# booz_main_v1_2.net
KiCad netlist of a schematic drawn in EAGLE
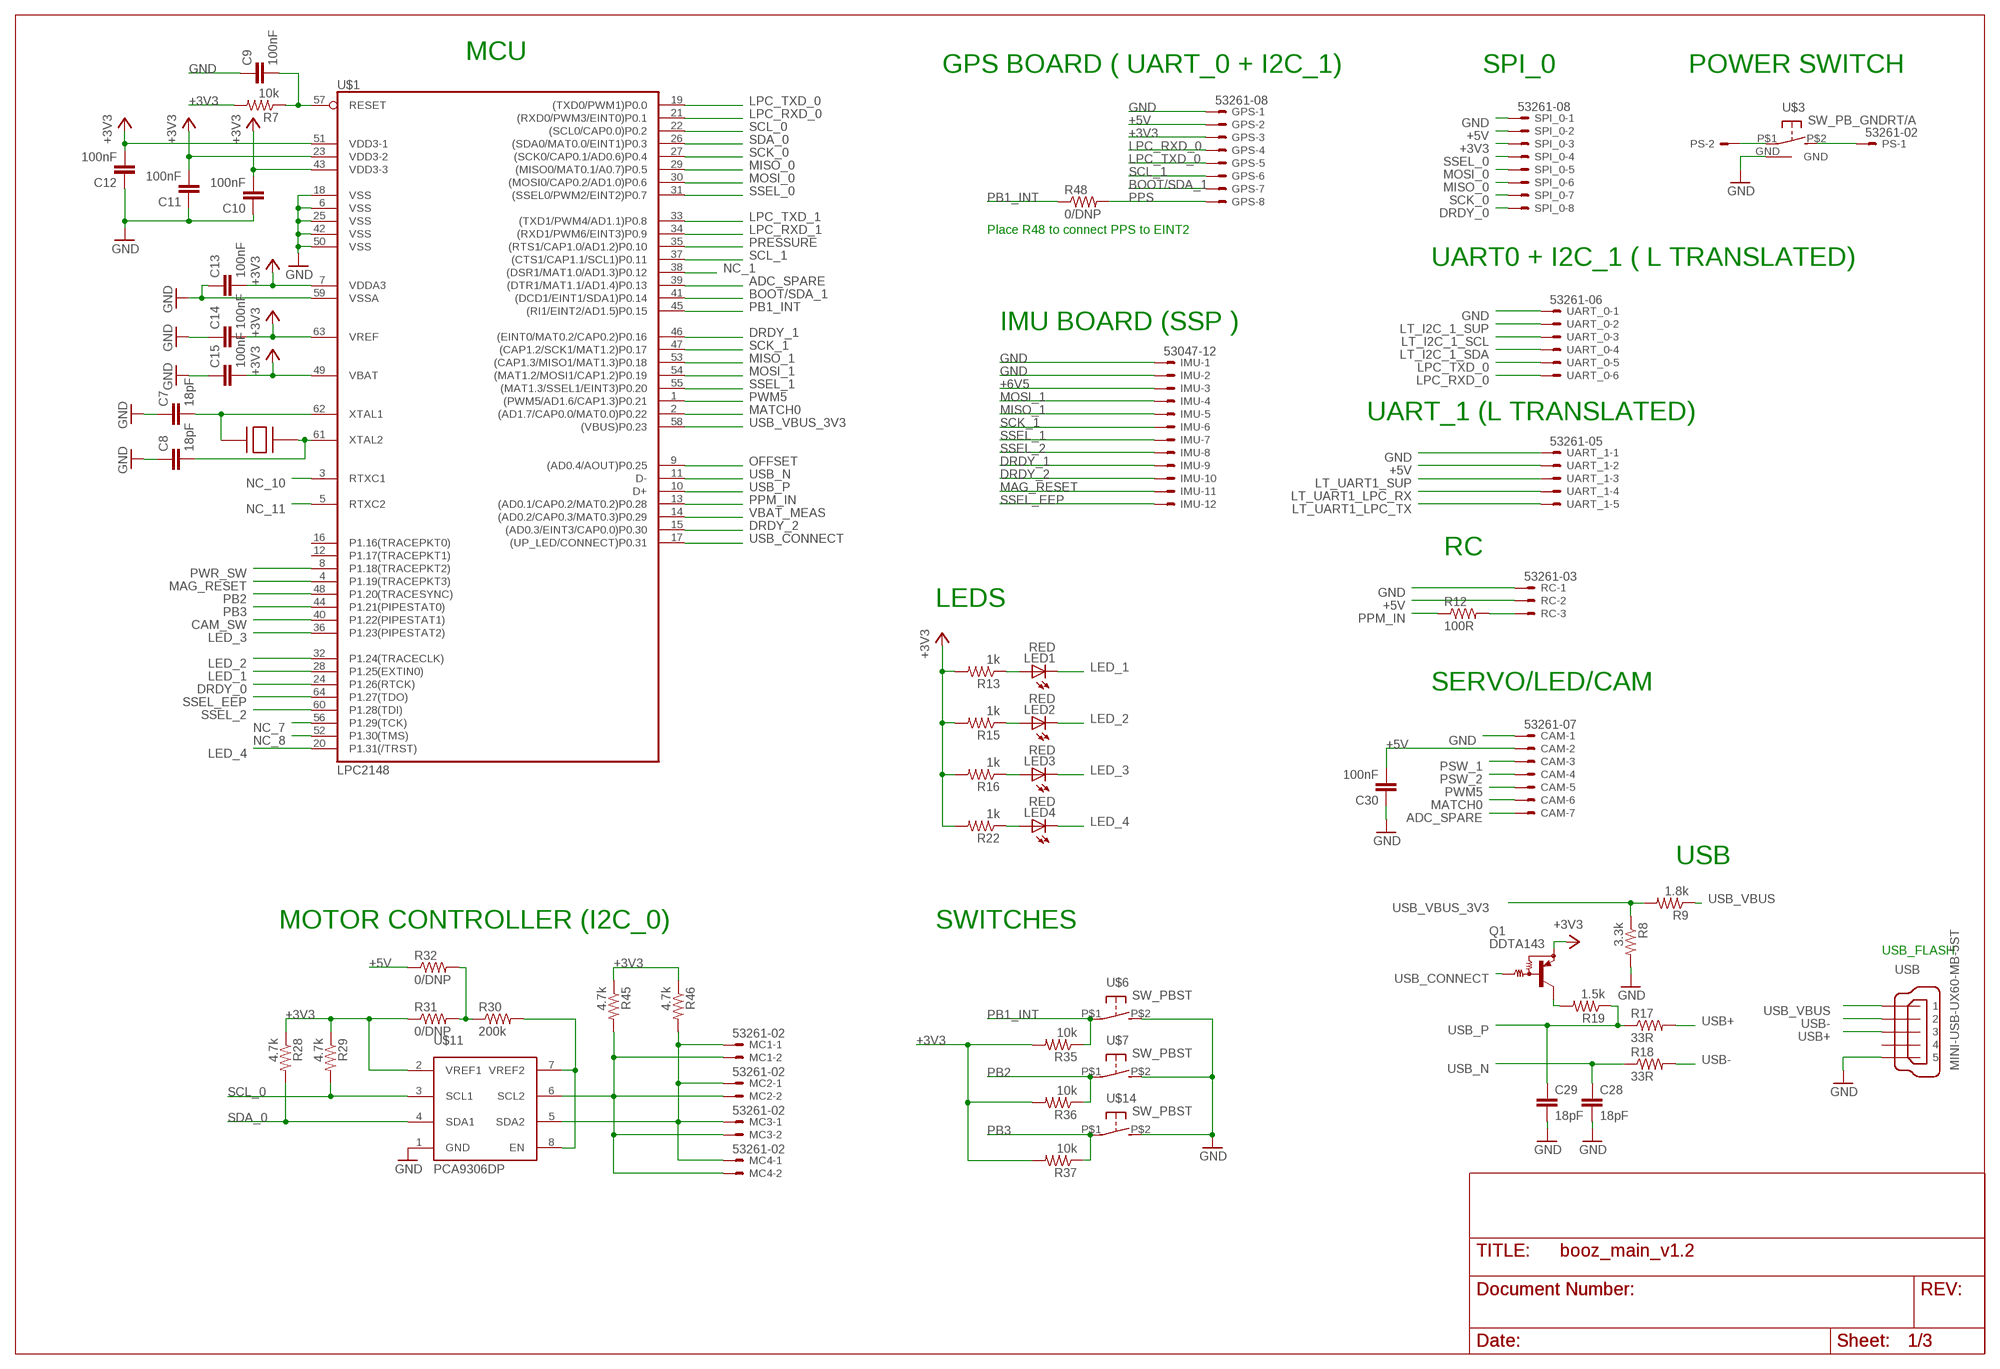
[diagram p0: schematic, sheet 1]
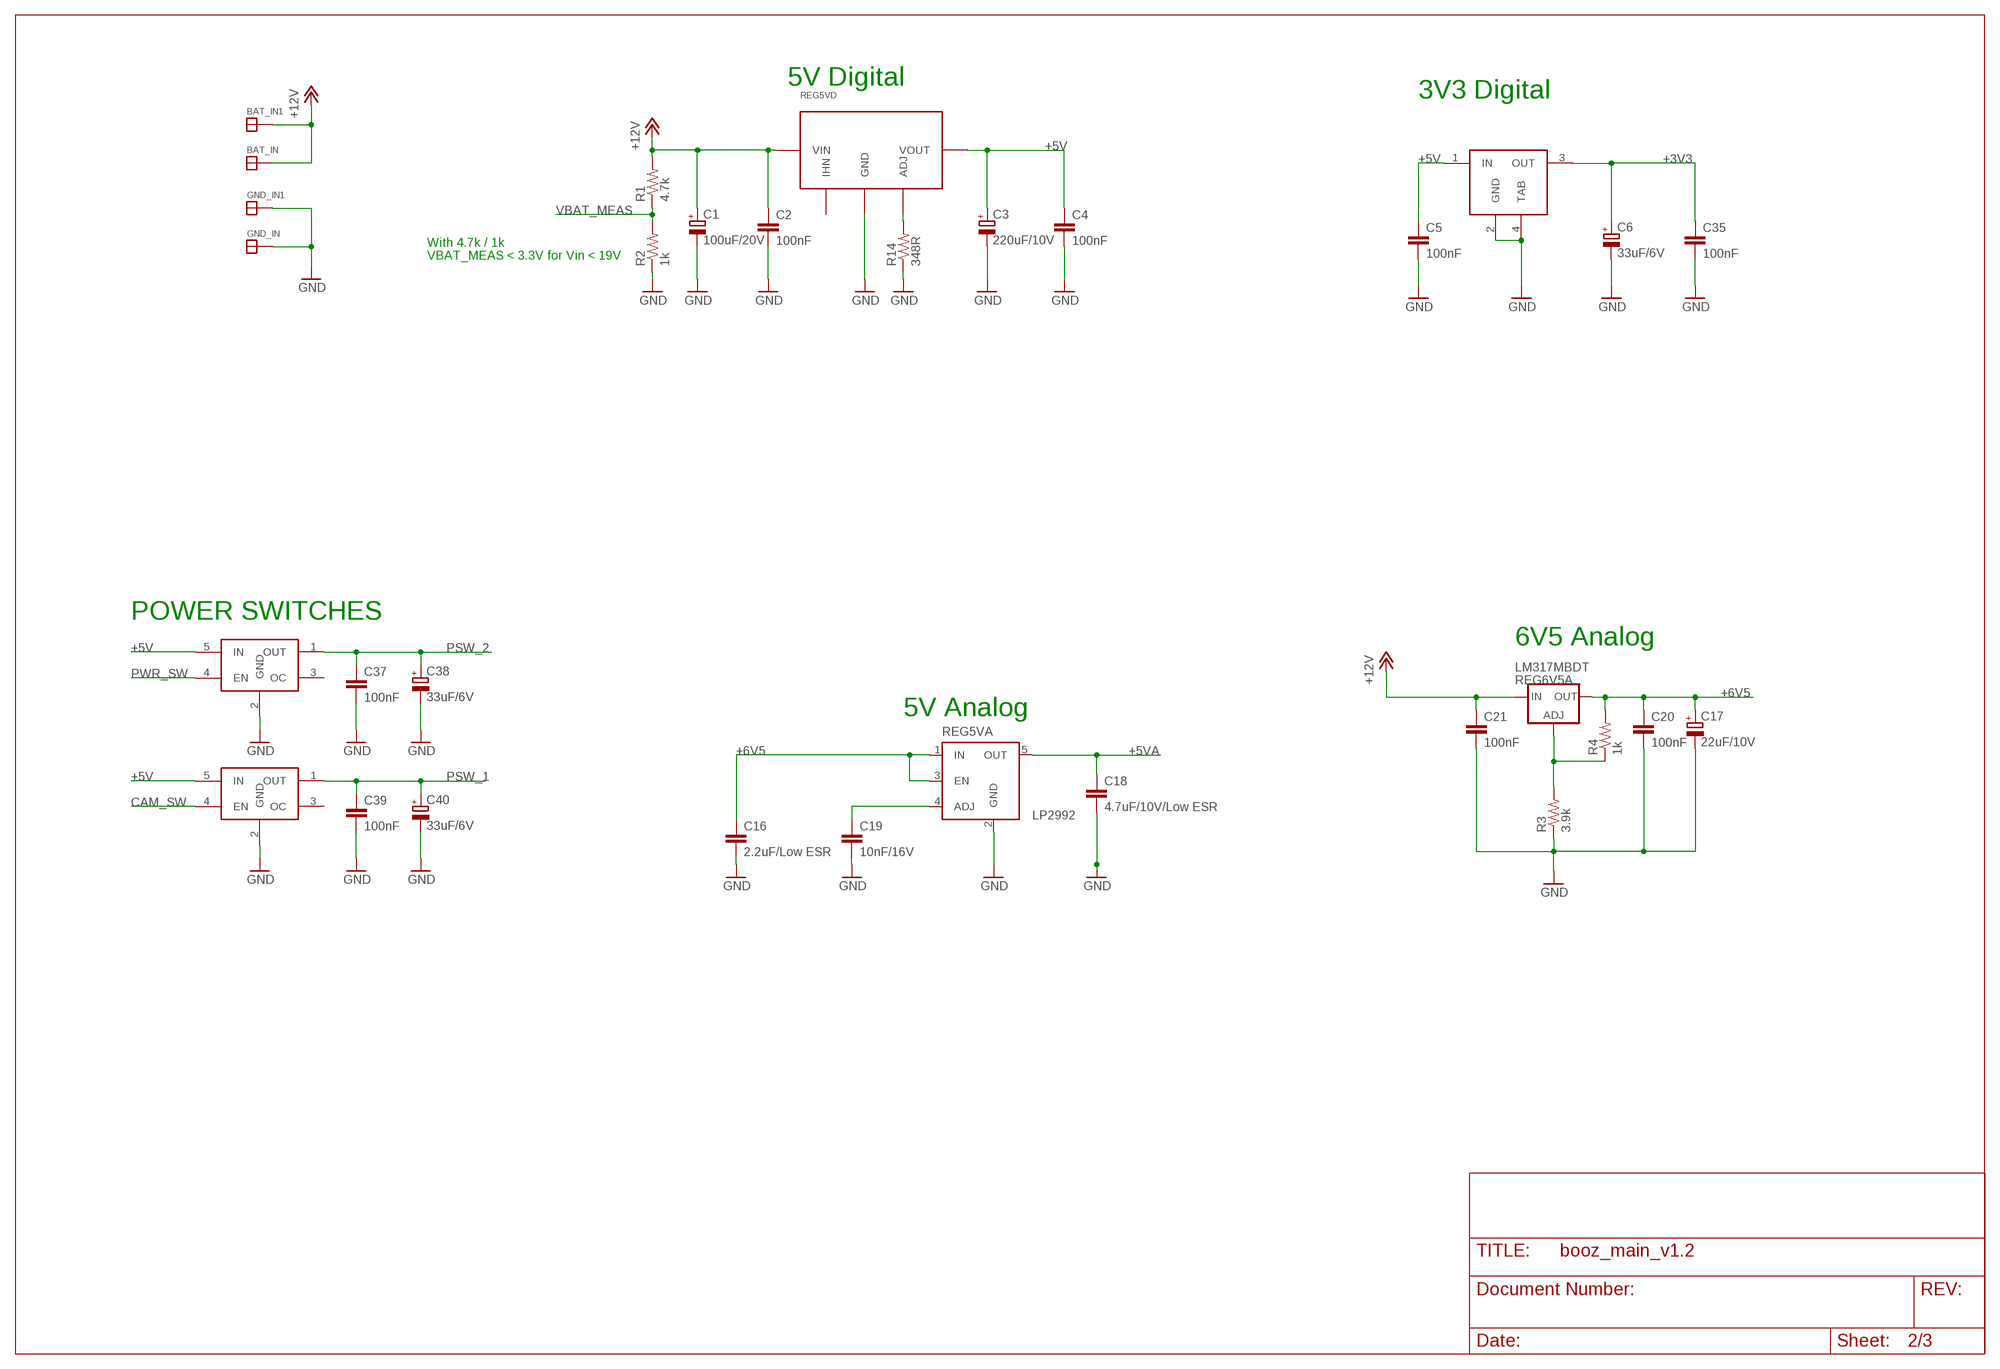
[diagram p1: schematic, sheet 2]
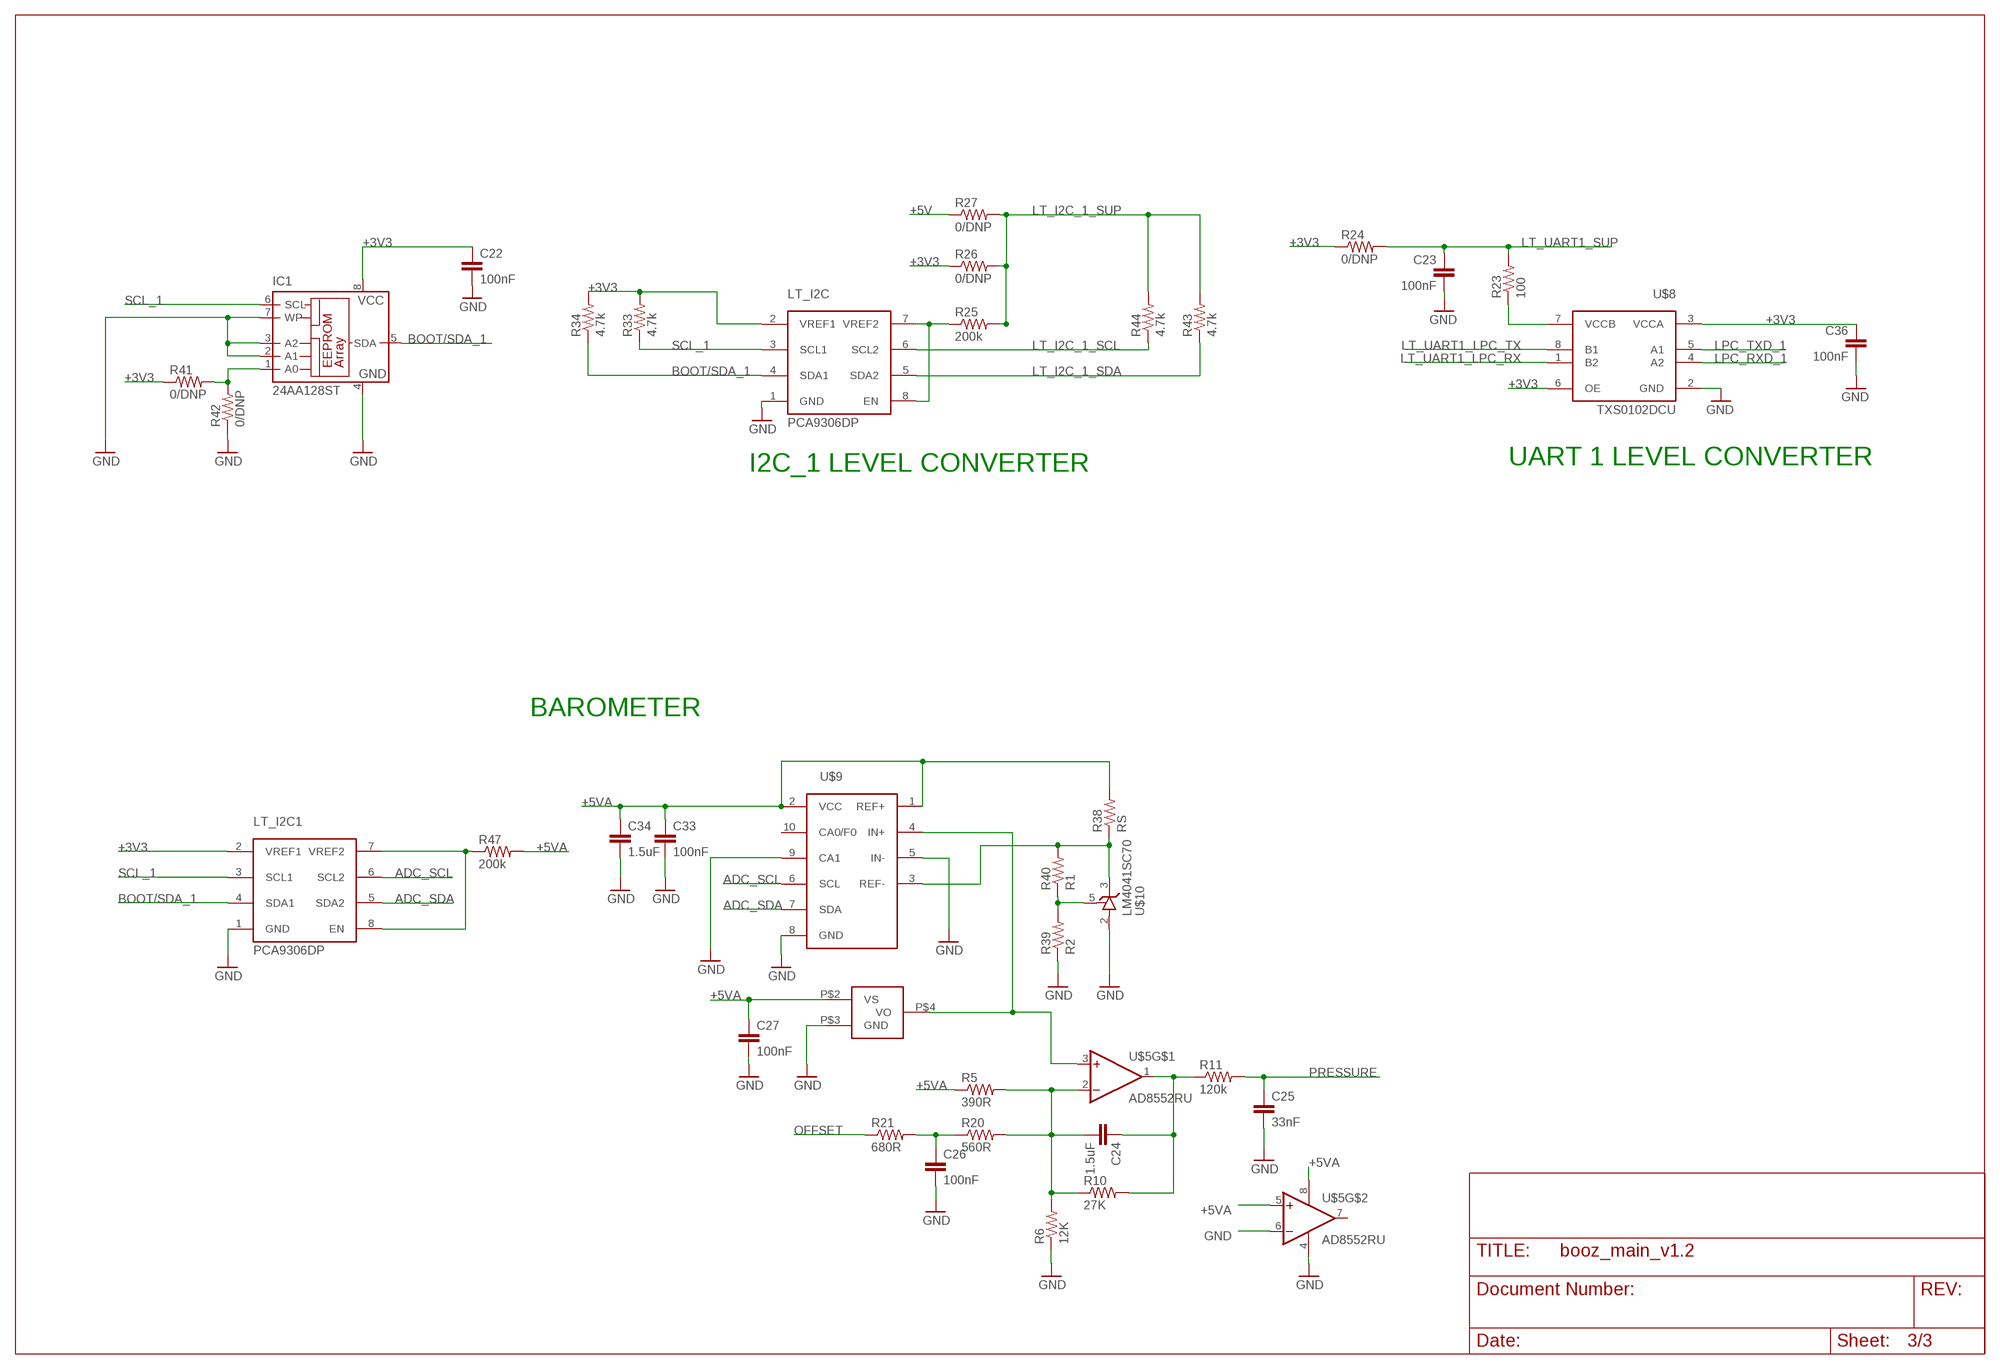
[diagram p2: schematic, sheet 3]

(export (version "E")
  (design (tool "Eeschema 10.0.6"))
  (components
    (comp (ref "BAT_IN")
      (value "SOLDER_PAD150_75")
      (footprint "eagle-import:SOLD_PAD_150_75")
      (libsource (lib "eagle-import") (part "SOLDER_PAD150_75"))
    )
    (comp (ref "BAT_IN1")
      (value "SOLDER_PAD150_75")
      (footprint "eagle-import:SOLD_PAD_150_75")
      (libsource (lib "eagle-import") (part "SOLDER_PAD150_75"))
    )
    (comp (ref "C1")
      (value "100uF/20V")
      (footprint "eagle-import:SMC_D")
      (libsource (lib "eagle-import") (part "CPOL-EUSMCD"))
    )
    (comp (ref "C2")
      (value "100nF")
      (footprint "eagle-import:C0603")
      (libsource (lib "eagle-import") (part "C-EUC0603"))
    )
    (comp (ref "C3")
      (value "220uF/10V")
      (footprint "eagle-import:SMC_D")
      (libsource (lib "eagle-import") (part "CPOL-EUSMCD"))
    )
    (comp (ref "C4")
      (value "100nF")
      (footprint "eagle-import:C0603")
      (libsource (lib "eagle-import") (part "C-EUC0603"))
    )
    (comp (ref "C5")
      (value "100nF")
      (footprint "eagle-import:C0603")
      (libsource (lib "eagle-import") (part "C-EUC0603"))
    )
    (comp (ref "C6")
      (value "33uF/6V")
      (footprint "eagle-import:CT3216")
      (libsource (lib "eagle-import") (part "CPOL-EUCT3216"))
    )
    (comp (ref "C16")
      (value "2.2uF/Low ESR")
      (footprint "eagle-import:C0603")
      (libsource (lib "eagle-import") (part "C-EUC0603"))
    )
    (comp (ref "C17")
      (value "22uF/10V")
      (footprint "eagle-import:CT3216")
      (libsource (lib "eagle-import") (part "CPOL-EUCT3216"))
    )
    (comp (ref "C18")
      (value "4.7uF/10V/Low ESR")
      (footprint "eagle-import:C0805K")
      (libsource (lib "eagle-import") (part "C-EUC0805K"))
    )
    (comp (ref "C19")
      (value "10nF/16V")
      (footprint "eagle-import:C0603K")
      (libsource (lib "eagle-import") (part "C-EUC0603K"))
    )
    (comp (ref "C20")
      (value "100nF")
      (footprint "eagle-import:C0603")
      (libsource (lib "eagle-import") (part "C-EUC0603"))
    )
    (comp (ref "C21")
      (value "100nF")
      (footprint "eagle-import:C0603")
      (libsource (lib "eagle-import") (part "C-EUC0603"))
    )
    (comp (ref "C35")
      (value "100nF")
      (footprint "eagle-import:C0603")
      (libsource (lib "eagle-import") (part "C-EUC0603"))
    )
    (comp (ref "C37")
      (value "100nF")
      (footprint "eagle-import:C0603")
      (libsource (lib "eagle-import") (part "C-EUC0603"))
    )
    (comp (ref "C38")
      (value "33uF/6V")
      (footprint "eagle-import:CT3216")
      (libsource (lib "eagle-import") (part "CPOL-EUCT3216"))
    )
    (comp (ref "C39")
      (value "100nF")
      (footprint "eagle-import:C0603")
      (libsource (lib "eagle-import") (part "C-EUC0603"))
    )
    (comp (ref "C40")
      (value "33uF/6V")
      (footprint "eagle-import:CT3216")
      (libsource (lib "eagle-import") (part "CPOL-EUCT3216"))
    )
    (comp (ref "GND_IN")
      (value "SOLDER_PAD150_75")
      (footprint "eagle-import:SOLD_PAD_150_75")
      (libsource (lib "eagle-import") (part "SOLDER_PAD150_75"))
    )
    (comp (ref "GND_IN1")
      (value "SOLDER_PAD150_75")
      (footprint "eagle-import:SOLD_PAD_150_75")
      (libsource (lib "eagle-import") (part "SOLDER_PAD150_75"))
    )
    (comp (ref "R1")
      (value "4.7k")
      (footprint "eagle-import:R0603")
      (libsource (lib "eagle-import") (part "R-US_R0603"))
    )
    (comp (ref "R2")
      (value "1k")
      (footprint "eagle-import:R0603")
      (libsource (lib "eagle-import") (part "R-US_R0603"))
    )
    (comp (ref "R3")
      (value "3.9k")
      (footprint "eagle-import:R0603")
      (libsource (lib "eagle-import") (part "R-US_R0603"))
    )
    (comp (ref "R4")
      (value "1k")
      (footprint "eagle-import:R0603")
      (libsource (lib "eagle-import") (part "R-US_R0603"))
    )
    (comp (ref "R14")
      (value "348R")
      (footprint "eagle-import:R0603")
      (libsource (lib "eagle-import") (part "R-US_R0603"))
    )
    (comp (ref "REG3V3D")
      (value "LM3940IMP-3.3")
      (footprint "eagle-import:SOT223-R")
      (libsource (lib "eagle-import") (part "LM3940IMP-3.3"))
    )
    (comp (ref "REG5VA")
      (value "LP2992")
      (footprint "eagle-import:SOT23-5")
      (libsource (lib "eagle-import") (part "MIC5219BM5"))
    )
    (comp (ref "REG5VD")
      (value "PTHTH")
      (footprint "eagle-import:PTH_TH")
      (libsource (lib "eagle-import") (part "PTHTH"))
    )
    (comp (ref "REG6V5A")
      (value "LM317MBDT")
      (footprint "eagle-import:DPACK")
      (libsource (lib "eagle-import") (part "LM317?MBDT"))
    )
    (comp (ref "U$12")
      (value "TPS2051B")
      (footprint "eagle-import:SOT23-5L")
      (libsource (lib "eagle-import") (part "TPS2051B"))
    )
    (comp (ref "U$13")
      (value "TPS2051B")
      (footprint "eagle-import:SOT23-5L")
      (libsource (lib "eagle-import") (part "TPS2051B"))
    )
    (comp (ref "C22")
      (value "100nF")
      (footprint "eagle-import:C0603")
      (libsource (lib "eagle-import") (part "C-EUC0603"))
    )
    (comp (ref "C23")
      (value "100nF")
      (footprint "eagle-import:C0603")
      (libsource (lib "eagle-import") (part "C-EUC0603"))
    )
    (comp (ref "C24")
      (value "1.5uF")
      (footprint "eagle-import:C0805")
      (libsource (lib "eagle-import") (part "C-EUC0805"))
    )
    (comp (ref "C25")
      (value "33nF")
      (footprint "eagle-import:C0805K")
      (libsource (lib "eagle-import") (part "C-EUC0805K"))
    )
    (comp (ref "C26")
      (value "100nF")
      (footprint "eagle-import:C0603")
      (libsource (lib "eagle-import") (part "C-EUC0603"))
    )
    (comp (ref "C27")
      (value "100nF")
      (footprint "eagle-import:C0603")
      (libsource (lib "eagle-import") (part "C-EUC0603"))
    )
    (comp (ref "C33")
      (value "100nF")
      (footprint "eagle-import:C0603")
      (libsource (lib "eagle-import") (part "C-EUC0603"))
    )
    (comp (ref "C34")
      (value "1.5uF")
      (footprint "eagle-import:C0805")
      (libsource (lib "eagle-import") (part "C-EUC0805"))
    )
    (comp (ref "C36")
      (value "100nF")
      (footprint "eagle-import:C0603")
      (libsource (lib "eagle-import") (part "C-EUC0603"))
    )
    (comp (ref "IC1")
      (value "24AA128ST")
      (footprint "eagle-import:TSSOP8")
      (libsource (lib "eagle-import") (part "24STAA128"))
    )
    (comp (ref "LT_I2C")
      (value "PCA9306DP")
      (footprint "eagle-import:TSSOP_B3")
      (libsource (lib "eagle-import") (part "PCA9306DP"))
    )
    (comp (ref "LT_I2C1")
      (value "PCA9306DP")
      (footprint "eagle-import:TSSOP_B3")
      (libsource (lib "eagle-import") (part "PCA9306DP"))
    )
    (comp (ref "R5")
      (value "390R")
      (footprint "eagle-import:R0603")
      (libsource (lib "eagle-import") (part "R-US_R0603"))
    )
    (comp (ref "R6")
      (value "12K")
      (footprint "eagle-import:R0603")
      (libsource (lib "eagle-import") (part "R-US_R0603"))
    )
    (comp (ref "R10")
      (value "27K")
      (footprint "eagle-import:R0603")
      (libsource (lib "eagle-import") (part "R-US_R0603"))
    )
    (comp (ref "R11")
      (value "120k")
      (footprint "eagle-import:R0603")
      (libsource (lib "eagle-import") (part "R-US_R0603"))
    )
    (comp (ref "R20")
      (value "560R")
      (footprint "eagle-import:R0603")
      (libsource (lib "eagle-import") (part "R-US_R0603"))
    )
    (comp (ref "R21")
      (value "680R")
      (footprint "eagle-import:R0603")
      (libsource (lib "eagle-import") (part "R-US_R0603"))
    )
    (comp (ref "R23")
      (value "100")
      (footprint "eagle-import:R0603")
      (libsource (lib "eagle-import") (part "R-US_R0603"))
    )
    (comp (ref "R24")
      (value "0/DNP")
      (footprint "eagle-import:R0603")
      (libsource (lib "eagle-import") (part "R-US_R0603"))
    )
    (comp (ref "R25")
      (value "200k")
      (footprint "eagle-import:R0603")
      (libsource (lib "eagle-import") (part "R-US_R0603"))
    )
    (comp (ref "R26")
      (value "0/DNP")
      (footprint "eagle-import:R0603")
      (libsource (lib "eagle-import") (part "R-US_R0603"))
    )
    (comp (ref "R27")
      (value "0/DNP")
      (footprint "eagle-import:R0603")
      (libsource (lib "eagle-import") (part "R-US_R0603"))
    )
    (comp (ref "R33")
      (value "4.7k")
      (footprint "eagle-import:R0603")
      (libsource (lib "eagle-import") (part "R-US_R0603"))
    )
    (comp (ref "R34")
      (value "4.7k")
      (footprint "eagle-import:R0603")
      (libsource (lib "eagle-import") (part "R-US_R0603"))
    )
    (comp (ref "R38")
      (value "RS")
      (footprint "eagle-import:R0603")
      (libsource (lib "eagle-import") (part "R-US_R0603"))
    )
    (comp (ref "R39")
      (value "R2")
      (footprint "eagle-import:R0603")
      (libsource (lib "eagle-import") (part "R-US_R0603"))
    )
    (comp (ref "R40")
      (value "R1")
      (footprint "eagle-import:R0603")
      (libsource (lib "eagle-import") (part "R-US_R0603"))
    )
    (comp (ref "R41")
      (value "0/DNP")
      (footprint "eagle-import:R0603")
      (libsource (lib "eagle-import") (part "R-US_R0603"))
    )
    (comp (ref "R42")
      (value "0/DNP")
      (footprint "eagle-import:R0603")
      (libsource (lib "eagle-import") (part "R-US_R0603"))
    )
    (comp (ref "R43")
      (value "4.7k")
      (footprint "eagle-import:R0603")
      (libsource (lib "eagle-import") (part "R-US_R0603"))
    )
    (comp (ref "R44")
      (value "4.7k")
      (footprint "eagle-import:R0603")
      (libsource (lib "eagle-import") (part "R-US_R0603"))
    )
    (comp (ref "R47")
      (value "200k")
      (footprint "eagle-import:R0603")
      (libsource (lib "eagle-import") (part "R-US_R0603"))
    )
    (comp (ref "U$2")
      (value "MPX6115")
      (footprint "eagle-import:CASE_1317")
      (libsource (lib "eagle-import") (part "MPX6115"))
    )
    (comp (ref "U$5")
      (value "AD8552RU")
      (footprint "eagle-import:TSSOP8")
      (libsource (lib "eagle-import") (part "AD8552RU"))
    )
    (comp (ref "U$8")
      (value "TXS0102DCU")
      (footprint "eagle-import:US8")
      (libsource (lib "eagle-import") (part "TXS0102DCU"))
    )
    (comp (ref "U$9")
      (value "LTC2485")
      (footprint "eagle-import:DFN10")
      (libsource (lib "eagle-import") (part "LTC2485"))
    )
    (comp (ref "U$10")
      (value "LM4041SC70")
      (footprint "eagle-import:SC70-5L")
      (libsource (lib "eagle-import") (part "LM4041SC70"))
    )
    (comp (ref "C7")
      (value "18pF")
      (footprint "eagle-import:C0603")
      (libsource (lib "eagle-import") (part "C-EUC0603"))
    )
    (comp (ref "C8")
      (value "18pF")
      (footprint "eagle-import:C0603")
      (libsource (lib "eagle-import") (part "C-EUC0603"))
    )
    (comp (ref "C9")
      (value "100nF")
      (footprint "eagle-import:C0603")
      (libsource (lib "eagle-import") (part "C-EUC0603"))
    )
    (comp (ref "C10")
      (value "100nF")
      (footprint "eagle-import:C0603")
      (libsource (lib "eagle-import") (part "C-EUC0603"))
    )
    (comp (ref "C11")
      (value "100nF")
      (footprint "eagle-import:C0603")
      (libsource (lib "eagle-import") (part "C-EUC0603"))
    )
    (comp (ref "C12")
      (value "100nF")
      (footprint "eagle-import:C0603")
      (libsource (lib "eagle-import") (part "C-EUC0603"))
    )
    (comp (ref "C13")
      (value "100nF")
      (footprint "eagle-import:C0603")
      (libsource (lib "eagle-import") (part "C-EUC0603"))
    )
    (comp (ref "C14")
      (value "100nF")
      (footprint "eagle-import:C0603")
      (libsource (lib "eagle-import") (part "C-EUC0603"))
    )
    (comp (ref "C15")
      (value "100nF")
      (footprint "eagle-import:C0603")
      (libsource (lib "eagle-import") (part "C-EUC0603"))
    )
    (comp (ref "C28")
      (value "18pF")
      (footprint "eagle-import:C0603")
      (libsource (lib "eagle-import") (part "C-EUC0603"))
    )
    (comp (ref "C29")
      (value "18pF")
      (footprint "eagle-import:C0603")
      (libsource (lib "eagle-import") (part "C-EUC0603"))
    )
    (comp (ref "C30")
      (value "100nF")
      (footprint "eagle-import:C0603")
      (libsource (lib "eagle-import") (part "C-EUC0603"))
    )
    (comp (ref "CAM")
      (value "53261-07")
      (footprint "eagle-import:53261-07")
      (libsource (lib "eagle-import") (part "53?-07261"))
    )
    (comp (ref "GPS")
      (value "53261-08")
      (footprint "eagle-import:53261-08")
      (libsource (lib "eagle-import") (part "53?-08261"))
    )
    (comp (ref "IMU")
      (value "53047-12")
      (footprint "eagle-import:53047-12")
      (libsource (lib "eagle-import") (part "53?-12047"))
    )
    (comp (ref "LED1")
      (value "RED")
      (footprint "eagle-import:CHIP-LED0805")
      (libsource (lib "eagle-import") (part "LEDCHIP-LED0805"))
    )
    (comp (ref "LED2")
      (value "RED")
      (footprint "eagle-import:CHIP-LED0805")
      (libsource (lib "eagle-import") (part "LEDCHIP-LED0805"))
    )
    (comp (ref "LED3")
      (value "RED")
      (footprint "eagle-import:CHIP-LED0805")
      (libsource (lib "eagle-import") (part "LEDCHIP-LED0805"))
    )
    (comp (ref "LED4")
      (value "RED")
      (footprint "eagle-import:CHIP-LED0805")
      (libsource (lib "eagle-import") (part "LEDCHIP-LED0805"))
    )
    (comp (ref "MC1")
      (value "53261-02")
      (footprint "eagle-import:53261-02")
      (libsource (lib "eagle-import") (part "53?-02261"))
    )
    (comp (ref "MC2")
      (value "53261-02")
      (footprint "eagle-import:53261-02")
      (libsource (lib "eagle-import") (part "53?-02261"))
    )
    (comp (ref "MC3")
      (value "53261-02")
      (footprint "eagle-import:53261-02")
      (libsource (lib "eagle-import") (part "53?-02261"))
    )
    (comp (ref "MC4")
      (value "53261-02")
      (footprint "eagle-import:53261-02")
      (libsource (lib "eagle-import") (part "53?-02261"))
    )
    (comp (ref "PS")
      (value "53261-02")
      (footprint "eagle-import:53261-02")
      (libsource (lib "eagle-import") (part "53?-02261"))
    )
    (comp (ref "Q1")
      (value "DDTA143")
      (footprint "eagle-import:SC59-BEC")
      (libsource (lib "eagle-import") (part "MUN2111T1"))
    )
    (comp (ref "R7")
      (value "10k")
      (footprint "eagle-import:R0603")
      (libsource (lib "eagle-import") (part "R-US_R0603"))
    )
    (comp (ref "R8")
      (value "3.3k")
      (footprint "eagle-import:R0603")
      (libsource (lib "eagle-import") (part "R-US_R0603"))
    )
    (comp (ref "R9")
      (value "1.8k")
      (footprint "eagle-import:R0603")
      (libsource (lib "eagle-import") (part "R-US_R0603"))
    )
    (comp (ref "R12")
      (value "100R")
      (footprint "eagle-import:R0603")
      (libsource (lib "eagle-import") (part "R-US_R0603"))
    )
    (comp (ref "R13")
      (value "1k")
      (footprint "eagle-import:R0603")
      (libsource (lib "eagle-import") (part "R-US_R0603"))
    )
    (comp (ref "R15")
      (value "1k")
      (footprint "eagle-import:R0603")
      (libsource (lib "eagle-import") (part "R-US_R0603"))
    )
    (comp (ref "R16")
      (value "1k")
      (footprint "eagle-import:R0603")
      (libsource (lib "eagle-import") (part "R-US_R0603"))
    )
    (comp (ref "R17")
      (value "33R")
      (footprint "eagle-import:R0603")
      (libsource (lib "eagle-import") (part "R-US_R0603"))
    )
    (comp (ref "R18")
      (value "33R")
      (footprint "eagle-import:R0603")
      (libsource (lib "eagle-import") (part "R-US_R0603"))
    )
    (comp (ref "R19")
      (value "1.5k")
      (footprint "eagle-import:R0603")
      (libsource (lib "eagle-import") (part "R-US_R0603"))
    )
    (comp (ref "R22")
      (value "1k")
      (footprint "eagle-import:R0603")
      (libsource (lib "eagle-import") (part "R-US_R0603"))
    )
    (comp (ref "R28")
      (value "4.7k")
      (footprint "eagle-import:R0603")
      (libsource (lib "eagle-import") (part "R-US_R0603"))
    )
    (comp (ref "R29")
      (value "4.7k")
      (footprint "eagle-import:R0603")
      (libsource (lib "eagle-import") (part "R-US_R0603"))
    )
    (comp (ref "R30")
      (value "200k")
      (footprint "eagle-import:R0603")
      (libsource (lib "eagle-import") (part "R-US_R0603"))
    )
    (comp (ref "R31")
      (value "0/DNP")
      (footprint "eagle-import:R0603")
      (libsource (lib "eagle-import") (part "R-US_R0603"))
    )
    (comp (ref "R32")
      (value "0/DNP")
      (footprint "eagle-import:R0603")
      (libsource (lib "eagle-import") (part "R-US_R0603"))
    )
    (comp (ref "R35")
      (value "10k")
      (footprint "eagle-import:R0603")
      (libsource (lib "eagle-import") (part "R-US_R0603"))
    )
    (comp (ref "R36")
      (value "10k")
      (footprint "eagle-import:R0603")
      (libsource (lib "eagle-import") (part "R-US_R0603"))
    )
    (comp (ref "R37")
      (value "10k")
      (footprint "eagle-import:R0603")
      (libsource (lib "eagle-import") (part "R-US_R0603"))
    )
    (comp (ref "R45")
      (value "4.7k")
      (footprint "eagle-import:R0603")
      (libsource (lib "eagle-import") (part "R-US_R0603"))
    )
    (comp (ref "R46")
      (value "4.7k")
      (footprint "eagle-import:R0603")
      (libsource (lib "eagle-import") (part "R-US_R0603"))
    )
    (comp (ref "R48")
      (value "0/DNP")
      (footprint "eagle-import:R0603")
      (libsource (lib "eagle-import") (part "R-US_R0603"))
    )
    (comp (ref "RC")
      (value "53261-03")
      (footprint "eagle-import:53261-03")
      (libsource (lib "eagle-import") (part "53?-03261"))
    )
    (comp (ref "SPI_0")
      (value "53261-08")
      (footprint "eagle-import:53261-08")
      (libsource (lib "eagle-import") (part "53?-08261"))
    )
    (comp (ref "U$1")
      (value "LPC2148")
      (footprint "eagle-import:SQFP-S-10X10-64")
      (libsource (lib "eagle-import") (part "LPC2148"))
    )
    (comp (ref "U$3")
      (value "SW_PB_GNDRT/A")
      (footprint "eagle-import:B3U-3100P")
      (libsource (lib "eagle-import") (part "SW_PB_GNDRT/A"))
    )
    (comp (ref "U$4")
      (value "CRYSTAL_CTS")
      (footprint "eagle-import:CTS_CRYSTAL")
      (libsource (lib "eagle-import") (part "CRYSTAL_CTS"))
    )
    (comp (ref "U$6")
      (value "SW_PBST")
      (footprint "eagle-import:B3U-1000P")
      (libsource (lib "eagle-import") (part "SW_PBST"))
    )
    (comp (ref "U$7")
      (value "SW_PBST")
      (footprint "eagle-import:B3U-1000P")
      (libsource (lib "eagle-import") (part "SW_PBST"))
    )
    (comp (ref "U$11")
      (value "PCA9306DP")
      (footprint "eagle-import:TSSOP_B3")
      (libsource (lib "eagle-import") (part "PCA9306DP"))
    )
    (comp (ref "U$14")
      (value "SW_PBST")
      (footprint "eagle-import:B3U-1000P")
      (libsource (lib "eagle-import") (part "SW_PBST"))
    )
    (comp (ref "UART_0")
      (value "53261-06")
      (footprint "eagle-import:53261-06")
      (libsource (lib "eagle-import") (part "53?-06261"))
    )
    (comp (ref "UART_1")
      (value "53261-05")
      (footprint "eagle-import:53261-05")
      (libsource (lib "eagle-import") (part "53?-05261"))
    )
    (comp (ref "USB")
      (value "MINI-USB-UX60-MB-5ST")
      (footprint "eagle-import:UX60-MB-5ST")
      (libsource (lib "eagle-import") (part "MINI-USB-UX60-MB-5ST"))
    )
  )
  (nets
    (net (code "1") (name "+3V3") (class "Default")
      (node (ref "C10") (pin "2") (pinfunction "2_2") (pintype "passive"))
      (node (ref "C11") (pin "2") (pinfunction "2_2") (pintype "passive"))
      (node (ref "C12") (pin "2") (pinfunction "2_2") (pintype "passive"))
      (node (ref "C13") (pin "2") (pinfunction "2_2") (pintype "passive"))
      (node (ref "C14") (pin "2") (pinfunction "2_2") (pintype "passive"))
      (node (ref "C15") (pin "2") (pinfunction "2_2") (pintype "passive"))
      (node (ref "C22") (pin "1") (pinfunction "1_1") (pintype "passive"))
      (node (ref "C35") (pin "1") (pinfunction "1_1") (pintype "passive"))
      (node (ref "C36") (pin "1") (pinfunction "1_1") (pintype "passive"))
      (node (ref "C6") (pin "+") (pinfunction "+_+") (pintype "passive"))
      (node (ref "GPS") (pin "3") (pinfunction "S_3") (pintype "passive"))
      (node (ref "IC1") (pin "8") (pinfunction "VCC_8") (pintype "power_in"))
      (node (ref "LT_I2C") (pin "2") (pinfunction "VREF1_2") (pintype "bidirectional"))
      (node (ref "LT_I2C1") (pin "2") (pinfunction "VREF1_2") (pintype "bidirectional"))
      (node (ref "Q1") (pin "E") (pinfunction "E_E") (pintype "passive"))
      (node (ref "R13") (pin "2") (pinfunction "2_2") (pintype "passive"))
      (node (ref "R15") (pin "2") (pinfunction "2_2") (pintype "passive"))
      (node (ref "R16") (pin "2") (pinfunction "2_2") (pintype "passive"))
      (node (ref "R22") (pin "2") (pinfunction "2_2") (pintype "passive"))
      (node (ref "R24") (pin "1") (pinfunction "1_1") (pintype "passive"))
      (node (ref "R26") (pin "1") (pinfunction "1_1") (pintype "passive"))
      (node (ref "R28") (pin "1") (pinfunction "1_1") (pintype "passive"))
      (node (ref "R29") (pin "1") (pinfunction "1_1") (pintype "passive"))
      (node (ref "R31") (pin "1") (pinfunction "1_1") (pintype "passive"))
      (node (ref "R33") (pin "2") (pinfunction "2_2") (pintype "passive"))
      (node (ref "R34") (pin "2") (pinfunction "2_2") (pintype "passive"))
      (node (ref "R35") (pin "2") (pinfunction "2_2") (pintype "passive"))
      (node (ref "R36") (pin "2") (pinfunction "2_2") (pintype "passive"))
      (node (ref "R37") (pin "2") (pinfunction "2_2") (pintype "passive"))
      (node (ref "R41") (pin "1") (pinfunction "1_1") (pintype "passive"))
      (node (ref "R45") (pin "1") (pinfunction "1_1") (pintype "passive"))
      (node (ref "R46") (pin "1") (pinfunction "1_1") (pintype "passive"))
      (node (ref "R7") (pin "2") (pinfunction "2_2") (pintype "passive"))
      (node (ref "REG3V3D") (pin "3") (pinfunction "OUT_3") (pintype "bidirectional"))
      (node (ref "SPI_0") (pin "3") (pinfunction "S_3") (pintype "passive"))
      (node (ref "U$1") (pin "23") (pinfunction "VDD3-2_23") (pintype "power_in"))
      (node (ref "U$1") (pin "43") (pinfunction "VDD3-3_43") (pintype "power_in"))
      (node (ref "U$1") (pin "49") (pinfunction "VBAT_49") (pintype "power_in"))
      (node (ref "U$1") (pin "51") (pinfunction "VDD3-1_51") (pintype "power_in"))
      (node (ref "U$1") (pin "63") (pinfunction "VREF_63") (pintype "input"))
      (node (ref "U$1") (pin "7") (pinfunction "VDDA3_7") (pintype "power_in"))
      (node (ref "U$11") (pin "2") (pinfunction "VREF1_2") (pintype "bidirectional"))
      (node (ref "U$8") (pin "3") (pinfunction "VCCA_3") (pintype "bidirectional"))
      (node (ref "U$8") (pin "6") (pinfunction "OE_6") (pintype "bidirectional"))
    )
    (net (code "2") (name "+5V") (class "Default")
      (node (ref "C3") (pin "+") (pinfunction "+_+") (pintype "passive"))
      (node (ref "C30") (pin "2") (pinfunction "2_2") (pintype "passive"))
      (node (ref "C4") (pin "1") (pinfunction "1_1") (pintype "passive"))
      (node (ref "C5") (pin "1") (pinfunction "1_1") (pintype "passive"))
      (node (ref "CAM") (pin "2") (pinfunction "S_2") (pintype "passive"))
      (node (ref "GPS") (pin "2") (pinfunction "S_2") (pintype "passive"))
      (node (ref "R27") (pin "1") (pinfunction "1_1") (pintype "passive"))
      (node (ref "R32") (pin "1") (pinfunction "1_1") (pintype "passive"))
      (node (ref "RC") (pin "2") (pinfunction "S_2") (pintype "passive"))
      (node (ref "REG3V3D") (pin "1") (pinfunction "IN_1") (pintype "bidirectional"))
      (node (ref "REG5VD") (pin "P$3") (pinfunction "VOUT_P$3") (pintype "bidirectional"))
      (node (ref "SPI_0") (pin "2") (pinfunction "S_2") (pintype "passive"))
      (node (ref "U$12") (pin "5") (pinfunction "IN_5") (pintype "bidirectional"))
      (node (ref "U$13") (pin "5") (pinfunction "IN_5") (pintype "bidirectional"))
      (node (ref "UART_1") (pin "2") (pinfunction "S_2") (pintype "passive"))
    )
    (net (code "3") (name "+5VA") (class "Default")
      (node (ref "C18") (pin "1") (pinfunction "1_1") (pintype "passive"))
      (node (ref "C27") (pin "1") (pinfunction "1_1") (pintype "passive"))
      (node (ref "C33") (pin "1") (pinfunction "1_1") (pintype "passive"))
      (node (ref "C34") (pin "1") (pinfunction "1_1") (pintype "passive"))
      (node (ref "R38") (pin "2") (pinfunction "2_2") (pintype "passive"))
      (node (ref "R47") (pin "2") (pinfunction "2_2") (pintype "passive"))
      (node (ref "R5") (pin "1") (pinfunction "1_1") (pintype "passive"))
      (node (ref "REG5VA") (pin "5") (pinfunction "OUT_5") (pintype "output"))
      (node (ref "U$2") (pin "P$2") (pinfunction "VS_P$2") (pintype "bidirectional"))
      (node (ref "U$5") (pin "5") (pinfunction "+IN_5") (pintype "input"))
      (node (ref "U$5") (pin "8") (pinfunction "V+_8") (pintype "power_in"))
      (node (ref "U$9") (pin "1") (pinfunction "REF+_1") (pintype "bidirectional"))
      (node (ref "U$9") (pin "2") (pinfunction "VCC_2") (pintype "bidirectional"))
    )
    (net (code "4") (name "+6V5") (class "Default")
      (node (ref "C16") (pin "1") (pinfunction "1_1") (pintype "passive"))
      (node (ref "C17") (pin "+") (pinfunction "+_+") (pintype "passive"))
      (node (ref "C20") (pin "1") (pinfunction "1_1") (pintype "passive"))
      (node (ref "IMU") (pin "3") (pinfunction "S_3") (pintype "passive"))
      (node (ref "R4") (pin "2") (pinfunction "2_2") (pintype "passive"))
      (node (ref "REG5VA") (pin "1") (pinfunction "IN_1") (pintype "input"))
      (node (ref "REG5VA") (pin "3") (pinfunction "EN_3") (pintype "input"))
      (node (ref "REG6V5A") (pin "4") (pinfunction "OUT_4") (pintype "passive"))
    )
    (net (code "5") (name "+12V") (class "Default")
      (node (ref "BAT_IN") (pin "P$1") (pinfunction "P$1_P$1") (pintype "bidirectional"))
      (node (ref "BAT_IN1") (pin "P$1") (pinfunction "P$1_P$1") (pintype "bidirectional"))
      (node (ref "C1") (pin "+") (pinfunction "+_+") (pintype "passive"))
      (node (ref "C2") (pin "1") (pinfunction "1_1") (pintype "passive"))
      (node (ref "C21") (pin "1") (pinfunction "1_1") (pintype "passive"))
      (node (ref "R1") (pin "2") (pinfunction "2_2") (pintype "passive"))
      (node (ref "REG5VD") (pin "P$1") (pinfunction "VIN_P$1") (pintype "bidirectional"))
      (node (ref "REG6V5A") (pin "3") (pinfunction "IN_3") (pintype "input"))
    )
    (net (code "6") (name "ADC_SCL") (class "Default")
      (node (ref "LT_I2C1") (pin "6") (pinfunction "SCL2_6") (pintype "bidirectional"))
      (node (ref "U$9") (pin "6") (pinfunction "SCL_6") (pintype "bidirectional"))
    )
    (net (code "7") (name "ADC_SDA") (class "Default")
      (node (ref "LT_I2C1") (pin "5") (pinfunction "SDA2_5") (pintype "bidirectional"))
      (node (ref "U$9") (pin "7") (pinfunction "SDA_7") (pintype "bidirectional"))
    )
    (net (code "8") (name "ADC_SPARE") (class "Default")
      (node (ref "CAM") (pin "7") (pinfunction "S_7") (pintype "passive"))
      (node (ref "U$1") (pin "39") (pinfunction "(DTR1/MAT1.1/AD1.4)P0.13_39") (pintype "bidirectional"))
    )
    (net (code "9") (name "BOOT{slash}SDA_1") (class "Default")
      (node (ref "GPS") (pin "7") (pinfunction "S_7") (pintype "passive"))
      (node (ref "IC1") (pin "5") (pinfunction "SDA_5") (pintype "bidirectional"))
      (node (ref "LT_I2C") (pin "4") (pinfunction "SDA1_4") (pintype "bidirectional"))
      (node (ref "LT_I2C1") (pin "4") (pinfunction "SDA1_4") (pintype "bidirectional"))
      (node (ref "R34") (pin "1") (pinfunction "1_1") (pintype "passive"))
      (node (ref "U$1") (pin "41") (pinfunction "(DCD1/EINT1/SDA1)P0.14_41") (pintype "bidirectional"))
    )
    (net (code "10") (name "CAM_SW") (class "Default")
      (node (ref "U$1") (pin "40") (pinfunction "P1.22(PIPESTAT1)_40") (pintype "bidirectional"))
      (node (ref "U$13") (pin "4") (pinfunction "EN_4") (pintype "bidirectional"))
    )
    (net (code "11") (name "DRDY_0") (class "Default")
      (node (ref "SPI_0") (pin "8") (pinfunction "S_8") (pintype "passive"))
      (node (ref "U$1") (pin "24") (pinfunction "P1.26(RTCK)_24") (pintype "bidirectional"))
    )
    (net (code "12") (name "DRDY_1") (class "Default")
      (node (ref "IMU") (pin "9") (pinfunction "S_9") (pintype "passive"))
      (node (ref "U$1") (pin "46") (pinfunction "(EINT0/MAT0.2/CAP0.2)P0.16_46") (pintype "bidirectional"))
    )
    (net (code "13") (name "DRDY_2") (class "Default")
      (node (ref "IMU") (pin "10") (pinfunction "S_10") (pintype "passive"))
      (node (ref "U$1") (pin "15") (pinfunction "(AD0.3/EINT3/CAP0.0)P0.30_15") (pintype "bidirectional"))
    )
    (net (code "14") (name "GND") (class "Default")
      (node (ref "C1") (pin "-") (pinfunction "-_-") (pintype "passive"))
      (node (ref "C10") (pin "1") (pinfunction "1_1") (pintype "passive"))
      (node (ref "C11") (pin "1") (pinfunction "1_1") (pintype "passive"))
      (node (ref "C12") (pin "1") (pinfunction "1_1") (pintype "passive"))
      (node (ref "C13") (pin "1") (pinfunction "1_1") (pintype "passive"))
      (node (ref "C14") (pin "1") (pinfunction "1_1") (pintype "passive"))
      (node (ref "C15") (pin "1") (pinfunction "1_1") (pintype "passive"))
      (node (ref "C16") (pin "2") (pinfunction "2_2") (pintype "passive"))
      (node (ref "C17") (pin "-") (pinfunction "-_-") (pintype "passive"))
      (node (ref "C18") (pin "2") (pinfunction "2_2") (pintype "passive"))
      (node (ref "C19") (pin "2") (pinfunction "2_2") (pintype "passive"))
      (node (ref "C2") (pin "2") (pinfunction "2_2") (pintype "passive"))
      (node (ref "C20") (pin "2") (pinfunction "2_2") (pintype "passive"))
      (node (ref "C21") (pin "2") (pinfunction "2_2") (pintype "passive"))
      (node (ref "C22") (pin "2") (pinfunction "2_2") (pintype "passive"))
      (node (ref "C23") (pin "2") (pinfunction "2_2") (pintype "passive"))
      (node (ref "C25") (pin "2") (pinfunction "2_2") (pintype "passive"))
      (node (ref "C26") (pin "2") (pinfunction "2_2") (pintype "passive"))
      (node (ref "C27") (pin "2") (pinfunction "2_2") (pintype "passive"))
      (node (ref "C28") (pin "2") (pinfunction "2_2") (pintype "passive"))
      (node (ref "C29") (pin "2") (pinfunction "2_2") (pintype "passive"))
      (node (ref "C3") (pin "-") (pinfunction "-_-") (pintype "passive"))
      (node (ref "C30") (pin "1") (pinfunction "1_1") (pintype "passive"))
      (node (ref "C33") (pin "2") (pinfunction "2_2") (pintype "passive"))
      (node (ref "C34") (pin "2") (pinfunction "2_2") (pintype "passive"))
      (node (ref "C35") (pin "2") (pinfunction "2_2") (pintype "passive"))
      (node (ref "C36") (pin "2") (pinfunction "2_2") (pintype "passive"))
      (node (ref "C37") (pin "2") (pinfunction "2_2") (pintype "passive"))
      (node (ref "C38") (pin "-") (pinfunction "-_-") (pintype "passive"))
      (node (ref "C39") (pin "2") (pinfunction "2_2") (pintype "passive"))
      (node (ref "C4") (pin "2") (pinfunction "2_2") (pintype "passive"))
      (node (ref "C40") (pin "-") (pinfunction "-_-") (pintype "passive"))
      (node (ref "C5") (pin "2") (pinfunction "2_2") (pintype "passive"))
      (node (ref "C6") (pin "-") (pinfunction "-_-") (pintype "passive"))
      (node (ref "C7") (pin "1") (pinfunction "1_1") (pintype "passive"))
      (node (ref "C8") (pin "1") (pinfunction "1_1") (pintype "passive"))
      (node (ref "C9") (pin "1") (pinfunction "1_1") (pintype "passive"))
      (node (ref "CAM") (pin "1") (pinfunction "S_1") (pintype "passive"))
      (node (ref "GND_IN") (pin "P$1") (pinfunction "P$1_P$1") (pintype "bidirectional"))
      (node (ref "GND_IN1") (pin "P$1") (pinfunction "P$1_P$1") (pintype "bidirectional"))
      (node (ref "GPS") (pin "1") (pinfunction "S_1") (pintype "passive"))
      (node (ref "IC1") (pin "2") (pinfunction "A1_2") (pintype "input"))
      (node (ref "IC1") (pin "3") (pinfunction "A2_3") (pintype "input"))
      (node (ref "IC1") (pin "4") (pinfunction "GND_4") (pintype "power_in"))
      (node (ref "IC1") (pin "7") (pinfunction "WP_7") (pintype "input"))
      (node (ref "IMU") (pin "1") (pinfunction "S_1") (pintype "passive"))
      (node (ref "IMU") (pin "2") (pinfunction "S_2") (pintype "passive"))
      (node (ref "LT_I2C") (pin "1") (pinfunction "GND_1") (pintype "bidirectional"))
      (node (ref "LT_I2C1") (pin "1") (pinfunction "GND_1") (pintype "bidirectional"))
      (node (ref "R14") (pin "1") (pinfunction "1_1") (pintype "passive"))
      (node (ref "R2") (pin "1") (pinfunction "1_1") (pintype "passive"))
      (node (ref "R3") (pin "1") (pinfunction "1_1") (pintype "passive"))
      (node (ref "R39") (pin "1") (pinfunction "1_1") (pintype "passive"))
      (node (ref "R42") (pin "1") (pinfunction "1_1") (pintype "passive"))
      (node (ref "R6") (pin "1") (pinfunction "1_1") (pintype "passive"))
      (node (ref "R8") (pin "2") (pinfunction "2_2") (pintype "passive"))
      (node (ref "RC") (pin "1") (pinfunction "S_1") (pintype "passive"))
      (node (ref "REG3V3D") (pin "2") (pinfunction "GND_2") (pintype "bidirectional"))
      (node (ref "REG3V3D") (pin "4") (pinfunction "TAB_4") (pintype "bidirectional"))
      (node (ref "REG5VA") (pin "2") (pinfunction "GND_2") (pintype "power_in"))
      (node (ref "REG5VD") (pin "P$2") (pinfunction "GND_P$2") (pintype "bidirectional"))
      (node (ref "SPI_0") (pin "1") (pinfunction "S_1") (pintype "passive"))
      (node (ref "U$1") (pin "18") (pinfunction "VSS_18") (pintype "power_in"))
      (node (ref "U$1") (pin "25") (pinfunction "VSS_25") (pintype "power_in"))
      (node (ref "U$1") (pin "42") (pinfunction "VSS_42") (pintype "power_in"))
      (node (ref "U$1") (pin "50") (pinfunction "VSS_50") (pintype "power_in"))
      (node (ref "U$1") (pin "59") (pinfunction "VSSA_59") (pintype "power_in"))
      (node (ref "U$1") (pin "6") (pinfunction "VSS_6") (pintype "power_in"))
      (node (ref "U$10") (pin "2") (pinfunction "A_2") (pintype "passive"))
      (node (ref "U$11") (pin "1") (pinfunction "GND_1") (pintype "bidirectional"))
      (node (ref "U$12") (pin "2") (pinfunction "GND_2") (pintype "bidirectional"))
      (node (ref "U$13") (pin "2") (pinfunction "GND_2") (pintype "bidirectional"))
      (node (ref "U$14") (pin "P$2") (pinfunction "S_P$2") (pintype "passive"))
      (node (ref "U$2") (pin "P$3") (pinfunction "GND_P$3") (pintype "bidirectional"))
      (node (ref "U$3") (pin "GND") (pinfunction "GND_GND") (pintype "passive"))
      (node (ref "U$5") (pin "4") (pinfunction "V-_4") (pintype "power_in"))
      (node (ref "U$5") (pin "6") (pinfunction "-IN_6") (pintype "input"))
      (node (ref "U$6") (pin "P$2") (pinfunction "S_P$2") (pintype "passive"))
      (node (ref "U$7") (pin "P$2") (pinfunction "S_P$2") (pintype "passive"))
      (node (ref "U$8") (pin "2") (pinfunction "GND_2") (pintype "bidirectional"))
      (node (ref "U$9") (pin "5") (pinfunction "IN-_5") (pintype "bidirectional"))
      (node (ref "U$9") (pin "8") (pinfunction "GND_8") (pintype "bidirectional"))
      (node (ref "U$9") (pin "9") (pinfunction "CA1_9") (pintype "bidirectional"))
      (node (ref "UART_0") (pin "1") (pinfunction "S_1") (pintype "passive"))
      (node (ref "UART_1") (pin "1") (pinfunction "S_1") (pintype "passive"))
      (node (ref "USB") (pin "5") (pinfunction "5_5") (pintype "input"))
    )
    (net (code "15") (name "LED_1") (class "Default")
      (node (ref "LED1") (pin "C") (pinfunction "C_C") (pintype "passive"))
      (node (ref "U$1") (pin "28") (pinfunction "P1.25(EXTIN0)_28") (pintype "bidirectional"))
    )
    (net (code "16") (name "LED_2") (class "Default")
      (node (ref "LED2") (pin "C") (pinfunction "C_C") (pintype "passive"))
      (node (ref "U$1") (pin "32") (pinfunction "P1.24(TRACECLK)_32") (pintype "bidirectional"))
    )
    (net (code "17") (name "LED_3") (class "Default")
      (node (ref "LED3") (pin "C") (pinfunction "C_C") (pintype "passive"))
      (node (ref "U$1") (pin "36") (pinfunction "P1.23(PIPESTAT2)_36") (pintype "bidirectional"))
    )
    (net (code "18") (name "LED_4") (class "Default")
      (node (ref "LED4") (pin "C") (pinfunction "C_C") (pintype "passive"))
      (node (ref "U$1") (pin "20") (pinfunction "P1.31(/TRST)_20") (pintype "bidirectional"))
    )
    (net (code "19") (name "LPC_RXD_0") (class "Default")
      (node (ref "GPS") (pin "4") (pinfunction "S_4") (pintype "passive"))
      (node (ref "U$1") (pin "21") (pinfunction "(RXD0/PWM3/EINT0)P0.1_21") (pintype "bidirectional"))
      (node (ref "UART_0") (pin "6") (pinfunction "S_6") (pintype "passive"))
    )
    (net (code "20") (name "LPC_RXD_1") (class "Default")
      (node (ref "U$1") (pin "34") (pinfunction "(RXD1/PWM6/EINT3)P0.9_34") (pintype "bidirectional"))
      (node (ref "U$8") (pin "4") (pinfunction "A2_4") (pintype "bidirectional"))
    )
    (net (code "21") (name "LPC_TXD_0") (class "Default")
      (node (ref "GPS") (pin "5") (pinfunction "S_5") (pintype "passive"))
      (node (ref "U$1") (pin "19") (pinfunction "(TXD0/PWM1)P0.0_19") (pintype "bidirectional"))
      (node (ref "UART_0") (pin "5") (pinfunction "S_5") (pintype "passive"))
    )
    (net (code "22") (name "LPC_TXD_1") (class "Default")
      (node (ref "U$1") (pin "33") (pinfunction "(TXD1/PWM4/AD1.1)P0.8_33") (pintype "bidirectional"))
      (node (ref "U$8") (pin "5") (pinfunction "A1_5") (pintype "bidirectional"))
    )
    (net (code "23") (name "LT_I2C_1_SCL") (class "Default")
      (node (ref "LT_I2C") (pin "6") (pinfunction "SCL2_6") (pintype "bidirectional"))
      (node (ref "R44") (pin "1") (pinfunction "1_1") (pintype "passive"))
      (node (ref "UART_0") (pin "3") (pinfunction "S_3") (pintype "passive"))
    )
    (net (code "24") (name "LT_I2C_1_SDA") (class "Default")
      (node (ref "LT_I2C") (pin "5") (pinfunction "SDA2_5") (pintype "bidirectional"))
      (node (ref "R43") (pin "1") (pinfunction "1_1") (pintype "passive"))
      (node (ref "UART_0") (pin "4") (pinfunction "S_4") (pintype "passive"))
    )
    (net (code "25") (name "LT_I2C_1_SUP") (class "Default")
      (node (ref "R25") (pin "2") (pinfunction "2_2") (pintype "passive"))
      (node (ref "R26") (pin "2") (pinfunction "2_2") (pintype "passive"))
      (node (ref "R27") (pin "2") (pinfunction "2_2") (pintype "passive"))
      (node (ref "R43") (pin "2") (pinfunction "2_2") (pintype "passive"))
      (node (ref "R44") (pin "2") (pinfunction "2_2") (pintype "passive"))
      (node (ref "UART_0") (pin "2") (pinfunction "S_2") (pintype "passive"))
    )
    (net (code "26") (name "LT_UART1_LPC_RX") (class "Default")
      (node (ref "U$8") (pin "1") (pinfunction "B2_1") (pintype "bidirectional"))
      (node (ref "UART_1") (pin "4") (pinfunction "S_4") (pintype "passive"))
    )
    (net (code "27") (name "LT_UART1_LPC_TX") (class "Default")
      (node (ref "U$8") (pin "8") (pinfunction "B1_8") (pintype "bidirectional"))
      (node (ref "UART_1") (pin "5") (pinfunction "S_5") (pintype "passive"))
    )
    (net (code "28") (name "LT_UART1_SUP") (class "Default")
      (node (ref "C23") (pin "1") (pinfunction "1_1") (pintype "passive"))
      (node (ref "R23") (pin "2") (pinfunction "2_2") (pintype "passive"))
      (node (ref "R24") (pin "2") (pinfunction "2_2") (pintype "passive"))
      (node (ref "UART_1") (pin "3") (pinfunction "S_3") (pintype "passive"))
    )
    (net (code "29") (name "MAG_RESET") (class "Default")
      (node (ref "IMU") (pin "11") (pinfunction "S_11") (pintype "passive"))
      (node (ref "U$1") (pin "4") (pinfunction "P1.19(TRACEPKT3)_4") (pintype "bidirectional"))
    )
    (net (code "30") (name "MATCH0") (class "Default")
      (node (ref "CAM") (pin "6") (pinfunction "S_6") (pintype "passive"))
      (node (ref "U$1") (pin "2") (pinfunction "(AD1.7/CAP0.0/MAT0.0)P0.22_2") (pintype "bidirectional"))
    )
    (net (code "31") (name "MISO_0") (class "Default")
      (node (ref "SPI_0") (pin "6") (pinfunction "S_6") (pintype "passive"))
      (node (ref "U$1") (pin "29") (pinfunction "(MISO0/MAT0.1/A0.7)P0.5_29") (pintype "bidirectional"))
    )
    (net (code "32") (name "MISO_1") (class "Default")
      (node (ref "IMU") (pin "5") (pinfunction "S_5") (pintype "passive"))
      (node (ref "U$1") (pin "53") (pinfunction "(CAP1.3/MISO1/MAT1.3)P0.18_53") (pintype "bidirectional"))
    )
    (net (code "33") (name "MOSI_0") (class "Default")
      (node (ref "SPI_0") (pin "5") (pinfunction "S_5") (pintype "passive"))
      (node (ref "U$1") (pin "30") (pinfunction "(MOSI0/CAP0.2/AD1.0)P0.6_30") (pintype "bidirectional"))
    )
    (net (code "34") (name "MOSI_1") (class "Default")
      (node (ref "IMU") (pin "4") (pinfunction "S_4") (pintype "passive"))
      (node (ref "U$1") (pin "54") (pinfunction "(MAT1.2/MOSI1/CAP1.2)P0.19_54") (pintype "bidirectional"))
    )
    (net (code "35") (name "NC_1") (class "Default")
      (node (ref "U$1") (pin "38") (pinfunction "(DSR1/MAT1.0/AD1.3)P0.12_38") (pintype "bidirectional"))
    )
    (net (code "36") (name "NC_7") (class "Default")
      (node (ref "U$1") (pin "56") (pinfunction "P1.29(TCK)_56") (pintype "bidirectional"))
    )
    (net (code "37") (name "NC_8") (class "Default")
      (node (ref "U$1") (pin "52") (pinfunction "P1.30(TMS)_52") (pintype "bidirectional"))
    )
    (net (code "38") (name "NC_10") (class "Default")
      (node (ref "U$1") (pin "3") (pinfunction "RTXC1_3") (pintype "input"))
    )
    (net (code "39") (name "NC_11") (class "Default")
      (node (ref "U$1") (pin "5") (pinfunction "RTXC2_5") (pintype "output"))
    )
    (net (code "40") (name "Net-(C26-Pad1)") (class "Default")
      (node (ref "C26") (pin "1") (pinfunction "1_1") (pintype "passive"))
      (node (ref "R20") (pin "1") (pinfunction "1_1") (pintype "passive"))
      (node (ref "R21") (pin "2") (pinfunction "2_2") (pintype "passive"))
    )
    (net (code "41") (name "Net-(IC1-A0)") (class "Default")
      (node (ref "IC1") (pin "1") (pinfunction "A0_1") (pintype "input"))
      (node (ref "R41") (pin "2") (pinfunction "2_2") (pintype "passive"))
      (node (ref "R42") (pin "2") (pinfunction "2_2") (pintype "passive"))
    )
    (net (code "42") (name "Net-(LED1-PadA)") (class "Default")
      (node (ref "LED1") (pin "A") (pinfunction "A_A") (pintype "passive"))
      (node (ref "R13") (pin "1") (pinfunction "1_1") (pintype "passive"))
    )
    (net (code "43") (name "Net-(LED2-PadA)") (class "Default")
      (node (ref "LED2") (pin "A") (pinfunction "A_A") (pintype "passive"))
      (node (ref "R15") (pin "1") (pinfunction "1_1") (pintype "passive"))
    )
    (net (code "44") (name "Net-(LED3-PadA)") (class "Default")
      (node (ref "LED3") (pin "A") (pinfunction "A_A") (pintype "passive"))
      (node (ref "R16") (pin "1") (pinfunction "1_1") (pintype "passive"))
    )
    (net (code "45") (name "Net-(LED4-PadA)") (class "Default")
      (node (ref "LED4") (pin "A") (pinfunction "A_A") (pintype "passive"))
      (node (ref "R22") (pin "1") (pinfunction "1_1") (pintype "passive"))
    )
    (net (code "46") (name "Net-(LT_I2C-EN)") (class "Default")
      (node (ref "LT_I2C") (pin "7") (pinfunction "VREF2_7") (pintype "bidirectional"))
      (node (ref "LT_I2C") (pin "8") (pinfunction "EN_8") (pintype "bidirectional"))
      (node (ref "R25") (pin "1") (pinfunction "1_1") (pintype "passive"))
    )
    (net (code "47") (name "Net-(LT_I2C1-EN)") (class "Default")
      (node (ref "LT_I2C1") (pin "7") (pinfunction "VREF2_7") (pintype "bidirectional"))
      (node (ref "LT_I2C1") (pin "8") (pinfunction "EN_8") (pintype "bidirectional"))
      (node (ref "R47") (pin "1") (pinfunction "1_1") (pintype "passive"))
    )
    (net (code "48") (name "Net-(MC1A-S)") (class "Default")
      (node (ref "MC1") (pin "1") (pinfunction "S_1") (pintype "passive"))
      (node (ref "MC2") (pin "1") (pinfunction "S_1") (pintype "passive"))
      (node (ref "MC3") (pin "1") (pinfunction "S_1") (pintype "passive"))
      (node (ref "MC4") (pin "1") (pinfunction "S_1") (pintype "passive"))
      (node (ref "R46") (pin "2") (pinfunction "2_2") (pintype "passive"))
      (node (ref "U$11") (pin "5") (pinfunction "SDA2_5") (pintype "bidirectional"))
    )
    (net (code "49") (name "Net-(MC1B-S)") (class "Default")
      (node (ref "MC1") (pin "2") (pinfunction "S_2") (pintype "passive"))
      (node (ref "MC2") (pin "2") (pinfunction "S_2") (pintype "passive"))
      (node (ref "MC3") (pin "2") (pinfunction "S_2") (pintype "passive"))
      (node (ref "MC4") (pin "2") (pinfunction "S_2") (pintype "passive"))
      (node (ref "R45") (pin "2") (pinfunction "2_2") (pintype "passive"))
      (node (ref "U$11") (pin "6") (pinfunction "SCL2_6") (pintype "bidirectional"))
    )
    (net (code "50") (name "Net-(PSA-S)") (class "Default")
      (node (ref "PS") (pin "1") (pinfunction "S_1") (pintype "passive"))
      (node (ref "U$3") (pin "P$2") (pinfunction "S_P$2") (pintype "passive"))
    )
    (net (code "51") (name "Net-(PSB-S)") (class "Default")
      (node (ref "PS") (pin "2") (pinfunction "S_2") (pintype "passive"))
      (node (ref "U$3") (pin "P$1") (pinfunction "P_P$1") (pintype "passive"))
    )
    (net (code "52") (name "Net-(Q1-PadC)") (class "Default")
      (node (ref "Q1") (pin "C") (pinfunction "C_C") (pintype "passive"))
      (node (ref "R19") (pin "2") (pinfunction "2_2") (pintype "passive"))
    )
    (net (code "53") (name "Net-(R30-Pad1)") (class "Default")
      (node (ref "R30") (pin "1") (pinfunction "1_1") (pintype "passive"))
      (node (ref "R31") (pin "2") (pinfunction "2_2") (pintype "passive"))
      (node (ref "R32") (pin "2") (pinfunction "2_2") (pintype "passive"))
    )
    (net (code "54") (name "Net-(RCC-S)") (class "Default")
      (node (ref "R12") (pin "2") (pinfunction "2_2") (pintype "passive"))
      (node (ref "RC") (pin "3") (pinfunction "S_3") (pintype "passive"))
    )
    (net (code "55") (name "Net-(REG5VA-ADJ)") (class "Default")
      (node (ref "C19") (pin "1") (pinfunction "1_1") (pintype "passive"))
      (node (ref "REG5VA") (pin "4") (pinfunction "ADJ_4") (pintype "passive"))
    )
    (net (code "56") (name "Net-(REG5VD-ADJ)") (class "Default")
      (node (ref "R14") (pin "2") (pinfunction "2_2") (pintype "passive"))
      (node (ref "REG5VD") (pin "P$4") (pinfunction "ADJ_P$4") (pintype "bidirectional"))
    )
    (net (code "57") (name "Net-(REG6V5A-ADJ)") (class "Default")
      (node (ref "R3") (pin "2") (pinfunction "2_2") (pintype "passive"))
      (node (ref "R4") (pin "1") (pinfunction "1_1") (pintype "passive"))
      (node (ref "REG6V5A") (pin "1") (pinfunction "ADJ_1") (pintype "input"))
    )
    (net (code "58") (name "Net-(U$1-RESET)") (class "Default")
      (node (ref "C9") (pin "2") (pinfunction "2_2") (pintype "passive"))
      (node (ref "R7") (pin "1") (pinfunction "1_1") (pintype "passive"))
      (node (ref "U$1") (pin "57") (pinfunction "RESET_57") (pintype "input"))
    )
    (net (code "59") (name "Net-(U$1-XTAL1)") (class "Default")
      (node (ref "C7") (pin "2") (pinfunction "2_2") (pintype "passive"))
      (node (ref "U$1") (pin "62") (pinfunction "XTAL1_62") (pintype "input"))
      (node (ref "U$4") (pin "P$1") (pinfunction "P$1_P$1") (pintype "bidirectional"))
    )
    (net (code "60") (name "Net-(U$1-XTAL2)") (class "Default")
      (node (ref "C8") (pin "2") (pinfunction "2_2") (pintype "passive"))
      (node (ref "U$1") (pin "61") (pinfunction "XTAL2_61") (pintype "output"))
      (node (ref "U$4") (pin "P$3") (pinfunction "P$2_P$3") (pintype "bidirectional"))
    )
    (net (code "61") (name "Net-(U$2-VO)") (class "Default")
      (node (ref "U$2") (pin "P$4") (pinfunction "VO_P$4") (pintype "bidirectional"))
      (node (ref "U$5") (pin "3") (pinfunction "+IN_3") (pintype "input"))
      (node (ref "U$9") (pin "4") (pinfunction "IN+_4") (pintype "bidirectional"))
    )
    (net (code "62") (name "Net-(U$5A--IN)") (class "Default")
      (node (ref "C24") (pin "2") (pinfunction "2_2") (pintype "passive"))
      (node (ref "R10") (pin "1") (pinfunction "1_1") (pintype "passive"))
      (node (ref "R20") (pin "2") (pinfunction "2_2") (pintype "passive"))
      (node (ref "R5") (pin "2") (pinfunction "2_2") (pintype "passive"))
      (node (ref "R6") (pin "2") (pinfunction "2_2") (pintype "passive"))
      (node (ref "U$5") (pin "2") (pinfunction "-IN_2") (pintype "input"))
    )
    (net (code "63") (name "Net-(U$5A-OUT)") (class "Default")
      (node (ref "C24") (pin "1") (pinfunction "1_1") (pintype "passive"))
      (node (ref "R10") (pin "2") (pinfunction "2_2") (pintype "passive"))
      (node (ref "R11") (pin "1") (pinfunction "1_1") (pintype "passive"))
      (node (ref "U$5") (pin "1") (pinfunction "OUT_1") (pintype "output"))
    )
    (net (code "64") (name "Net-(U$8-VCCB)") (class "Default")
      (node (ref "R23") (pin "1") (pinfunction "1_1") (pintype "passive"))
      (node (ref "U$8") (pin "7") (pinfunction "VCCB_7") (pintype "bidirectional"))
    )
    (net (code "65") (name "Net-(U$10-C)") (class "Default")
      (node (ref "R38") (pin "1") (pinfunction "1_1") (pintype "passive"))
      (node (ref "R40") (pin "2") (pinfunction "2_2") (pintype "passive"))
      (node (ref "U$10") (pin "3") (pinfunction "C_3") (pintype "passive"))
      (node (ref "U$9") (pin "3") (pinfunction "REF-_3") (pintype "bidirectional"))
    )
    (net (code "66") (name "Net-(U$10-R)") (class "Default")
      (node (ref "R39") (pin "2") (pinfunction "2_2") (pintype "passive"))
      (node (ref "R40") (pin "1") (pinfunction "1_1") (pintype "passive"))
      (node (ref "U$10") (pin "5") (pinfunction "R_5") (pintype "passive"))
    )
    (net (code "67") (name "Net-(U$11-EN)") (class "Default")
      (node (ref "R30") (pin "2") (pinfunction "2_2") (pintype "passive"))
      (node (ref "U$11") (pin "7") (pinfunction "VREF2_7") (pintype "bidirectional"))
      (node (ref "U$11") (pin "8") (pinfunction "EN_8") (pintype "bidirectional"))
    )
    (net (code "68") (name "OFFSET") (class "Default")
      (node (ref "R21") (pin "1") (pinfunction "1_1") (pintype "passive"))
      (node (ref "U$1") (pin "9") (pinfunction "(AD0.4/AOUT)P0.25_9") (pintype "bidirectional"))
    )
    (net (code "69") (name "PB1_INT") (class "Default")
      (node (ref "R35") (pin "1") (pinfunction "1_1") (pintype "passive"))
      (node (ref "R48") (pin "1") (pinfunction "1_1") (pintype "passive"))
      (node (ref "U$1") (pin "45") (pinfunction "(RI1/EINT2/AD1.5)P0.15_45") (pintype "bidirectional"))
      (node (ref "U$6") (pin "P$1") (pinfunction "P_P$1") (pintype "passive"))
    )
    (net (code "70") (name "PB2") (class "Default")
      (node (ref "R36") (pin "1") (pinfunction "1_1") (pintype "passive"))
      (node (ref "U$1") (pin "48") (pinfunction "P1.20(TRACESYNC)_48") (pintype "bidirectional"))
      (node (ref "U$7") (pin "P$1") (pinfunction "P_P$1") (pintype "passive"))
    )
    (net (code "71") (name "PB3") (class "Default")
      (node (ref "R37") (pin "1") (pinfunction "1_1") (pintype "passive"))
      (node (ref "U$1") (pin "44") (pinfunction "P1.21(PIPESTAT0)_44") (pintype "bidirectional"))
      (node (ref "U$14") (pin "P$1") (pinfunction "P_P$1") (pintype "passive"))
    )
    (net (code "72") (name "PPM_IN") (class "Default")
      (node (ref "R12") (pin "1") (pinfunction "1_1") (pintype "passive"))
      (node (ref "U$1") (pin "13") (pinfunction "(AD0.1/CAP0.2/MAT0.2)P0.28_13") (pintype "bidirectional"))
    )
    (net (code "73") (name "PPS") (class "Default")
      (node (ref "GPS") (pin "8") (pinfunction "S_8") (pintype "passive"))
      (node (ref "R48") (pin "2") (pinfunction "2_2") (pintype "passive"))
    )
    (net (code "74") (name "PRESSURE") (class "Default")
      (node (ref "C25") (pin "1") (pinfunction "1_1") (pintype "passive"))
      (node (ref "R11") (pin "2") (pinfunction "2_2") (pintype "passive"))
      (node (ref "U$1") (pin "35") (pinfunction "(RTS1/CAP1.0/AD1.2)P0.10_35") (pintype "bidirectional"))
    )
    (net (code "75") (name "PSW_1") (class "Default")
      (node (ref "C39") (pin "1") (pinfunction "1_1") (pintype "passive"))
      (node (ref "C40") (pin "+") (pinfunction "+_+") (pintype "passive"))
      (node (ref "CAM") (pin "3") (pinfunction "S_3") (pintype "passive"))
      (node (ref "U$13") (pin "1") (pinfunction "OUT_1") (pintype "bidirectional"))
    )
    (net (code "76") (name "PSW_2") (class "Default")
      (node (ref "C37") (pin "1") (pinfunction "1_1") (pintype "passive"))
      (node (ref "C38") (pin "+") (pinfunction "+_+") (pintype "passive"))
      (node (ref "CAM") (pin "4") (pinfunction "S_4") (pintype "passive"))
      (node (ref "U$12") (pin "1") (pinfunction "OUT_1") (pintype "bidirectional"))
    )
    (net (code "77") (name "PWM5") (class "Default")
      (node (ref "CAM") (pin "5") (pinfunction "S_5") (pintype "passive"))
      (node (ref "U$1") (pin "1") (pinfunction "(PWM5/AD1.6/CAP1.3)P0.21_1") (pintype "bidirectional"))
    )
    (net (code "78") (name "PWR_SW") (class "Default")
      (node (ref "U$1") (pin "8") (pinfunction "P1.18(TRACEPKT2)_8") (pintype "bidirectional"))
      (node (ref "U$12") (pin "4") (pinfunction "EN_4") (pintype "bidirectional"))
    )
    (net (code "79") (name "SCK_0") (class "Default")
      (node (ref "SPI_0") (pin "7") (pinfunction "S_7") (pintype "passive"))
      (node (ref "U$1") (pin "27") (pinfunction "(SCK0/CAP0.1/AD0.6)P0.4_27") (pintype "bidirectional"))
    )
    (net (code "80") (name "SCK_1") (class "Default")
      (node (ref "IMU") (pin "6") (pinfunction "S_6") (pintype "passive"))
      (node (ref "U$1") (pin "47") (pinfunction "(CAP1.2/SCK1/MAT1.2)P0.17_47") (pintype "bidirectional"))
    )
    (net (code "81") (name "SCL_0") (class "Default")
      (node (ref "R29") (pin "2") (pinfunction "2_2") (pintype "passive"))
      (node (ref "U$1") (pin "22") (pinfunction "(SCL0/CAP0.0)P0.2_22") (pintype "bidirectional"))
      (node (ref "U$11") (pin "3") (pinfunction "SCL1_3") (pintype "bidirectional"))
    )
    (net (code "82") (name "SCL_1") (class "Default")
      (node (ref "GPS") (pin "6") (pinfunction "S_6") (pintype "passive"))
      (node (ref "IC1") (pin "6") (pinfunction "SCL_6") (pintype "input"))
      (node (ref "LT_I2C") (pin "3") (pinfunction "SCL1_3") (pintype "bidirectional"))
      (node (ref "LT_I2C1") (pin "3") (pinfunction "SCL1_3") (pintype "bidirectional"))
      (node (ref "R33") (pin "1") (pinfunction "1_1") (pintype "passive"))
      (node (ref "U$1") (pin "37") (pinfunction "(CTS1/CAP1.1/SCL1)P0.11_37") (pintype "bidirectional"))
    )
    (net (code "83") (name "SDA_0") (class "Default")
      (node (ref "R28") (pin "2") (pinfunction "2_2") (pintype "passive"))
      (node (ref "U$1") (pin "26") (pinfunction "(SDA0/MAT0.0/EINT1)P0.3_26") (pintype "bidirectional"))
      (node (ref "U$11") (pin "4") (pinfunction "SDA1_4") (pintype "bidirectional"))
    )
    (net (code "84") (name "SSEL_0") (class "Default")
      (node (ref "SPI_0") (pin "4") (pinfunction "S_4") (pintype "passive"))
      (node (ref "U$1") (pin "31") (pinfunction "(SSEL0/PWM2/EINT2)P0.7_31") (pintype "bidirectional"))
    )
    (net (code "85") (name "SSEL_1") (class "Default")
      (node (ref "IMU") (pin "7") (pinfunction "S_7") (pintype "passive"))
      (node (ref "U$1") (pin "55") (pinfunction "(MAT1.3/SSEL1/EINT3)P0.20_55") (pintype "bidirectional"))
    )
    (net (code "86") (name "SSEL_2") (class "Default")
      (node (ref "IMU") (pin "8") (pinfunction "S_8") (pintype "passive"))
      (node (ref "U$1") (pin "60") (pinfunction "P1.28(TDI)_60") (pintype "bidirectional"))
    )
    (net (code "87") (name "SSEL_EEP") (class "Default")
      (node (ref "IMU") (pin "12") (pinfunction "S_12") (pintype "passive"))
      (node (ref "U$1") (pin "64") (pinfunction "P1.27(TDO)_64") (pintype "bidirectional"))
    )
    (net (code "88") (name "USB+") (class "Default")
      (node (ref "R17") (pin "2") (pinfunction "2_2") (pintype "passive"))
      (node (ref "USB") (pin "3") (pinfunction "3_3") (pintype "input"))
    )
    (net (code "89") (name "USB-") (class "Default")
      (node (ref "R18") (pin "2") (pinfunction "2_2") (pintype "passive"))
      (node (ref "USB") (pin "2") (pinfunction "2_2") (pintype "input"))
    )
    (net (code "90") (name "USB_CONNECT") (class "Default")
      (node (ref "Q1") (pin "B") (pinfunction "B_B") (pintype "passive"))
      (node (ref "U$1") (pin "17") (pinfunction "(UP_LED/CONNECT)P0.31_17") (pintype "output"))
    )
    (net (code "91") (name "USB_N") (class "Default")
      (node (ref "C28") (pin "1") (pinfunction "1_1") (pintype "passive"))
      (node (ref "R18") (pin "1") (pinfunction "1_1") (pintype "passive"))
      (node (ref "U$1") (pin "11") (pinfunction "D-_11") (pintype "bidirectional"))
    )
    (net (code "92") (name "USB_P") (class "Default")
      (node (ref "C29") (pin "1") (pinfunction "1_1") (pintype "passive"))
      (node (ref "R17") (pin "1") (pinfunction "1_1") (pintype "passive"))
      (node (ref "R19") (pin "1") (pinfunction "1_1") (pintype "passive"))
      (node (ref "U$1") (pin "10") (pinfunction "D+_10") (pintype "bidirectional"))
    )
    (net (code "93") (name "USB_VBUS") (class "Default")
      (node (ref "R9") (pin "1") (pinfunction "1_1") (pintype "passive"))
      (node (ref "USB") (pin "1") (pinfunction "1_1") (pintype "input"))
    )
    (net (code "94") (name "USB_VBUS_3V3") (class "Default")
      (node (ref "R8") (pin "1") (pinfunction "1_1") (pintype "passive"))
      (node (ref "R9") (pin "2") (pinfunction "2_2") (pintype "passive"))
      (node (ref "U$1") (pin "58") (pinfunction "(VBUS)P0.23_58") (pintype "bidirectional"))
    )
    (net (code "95") (name "VBAT_MEAS") (class "Default")
      (node (ref "R1") (pin "1") (pinfunction "1_1") (pintype "passive"))
      (node (ref "R2") (pin "2") (pinfunction "2_2") (pintype "passive"))
      (node (ref "U$1") (pin "14") (pinfunction "(AD0.2/CAP0.3/MAT0.3)P0.29_14") (pintype "bidirectional"))
    )
    (net (code "96") (name "unconnected-(REG5VD-IHN-PadP$5)") (class "Default")
      (node (ref "REG5VD") (pin "P$5") (pinfunction "IHN_P$5") (pintype "bidirectional"))
    )
    (net (code "97") (name "unconnected-(U$1-P1.16(TRACEPKT0)-Pad16)") (class "Default")
      (node (ref "U$1") (pin "16") (pinfunction "P1.16(TRACEPKT0)_16") (pintype "bidirectional"))
    )
    (net (code "98") (name "unconnected-(U$1-P1.17(TRACEPKT1)-Pad12)") (class "Default")
      (node (ref "U$1") (pin "12") (pinfunction "P1.17(TRACEPKT1)_12") (pintype "bidirectional"))
    )
    (net (code "99") (name "unconnected-(U$5B-OUT-Pad7)") (class "Default")
      (node (ref "U$5") (pin "7") (pinfunction "OUT_7") (pintype "output"))
    )
    (net (code "100") (name "unconnected-(U$9-CA0{slash}F0-Pad10)") (class "Default")
      (node (ref "U$9") (pin "10") (pinfunction "CA0/F0_10") (pintype "bidirectional"))
    )
    (net (code "101") (name "unconnected-(U$12-OC-Pad3)") (class "Default")
      (node (ref "U$12") (pin "3") (pinfunction "OC_3") (pintype "bidirectional"))
    )
    (net (code "102") (name "unconnected-(U$13-OC-Pad3)") (class "Default")
      (node (ref "U$13") (pin "3") (pinfunction "OC_3") (pintype "bidirectional"))
    )
    (net (code "103") (name "unconnected-(USB-Pad4)") (class "Default")
      (node (ref "USB") (pin "4") (pinfunction "4_4") (pintype "input"))
    )
  )
)
